# KillSwitch.net
KiCad netlist of a schematic drawn in Altium Designer
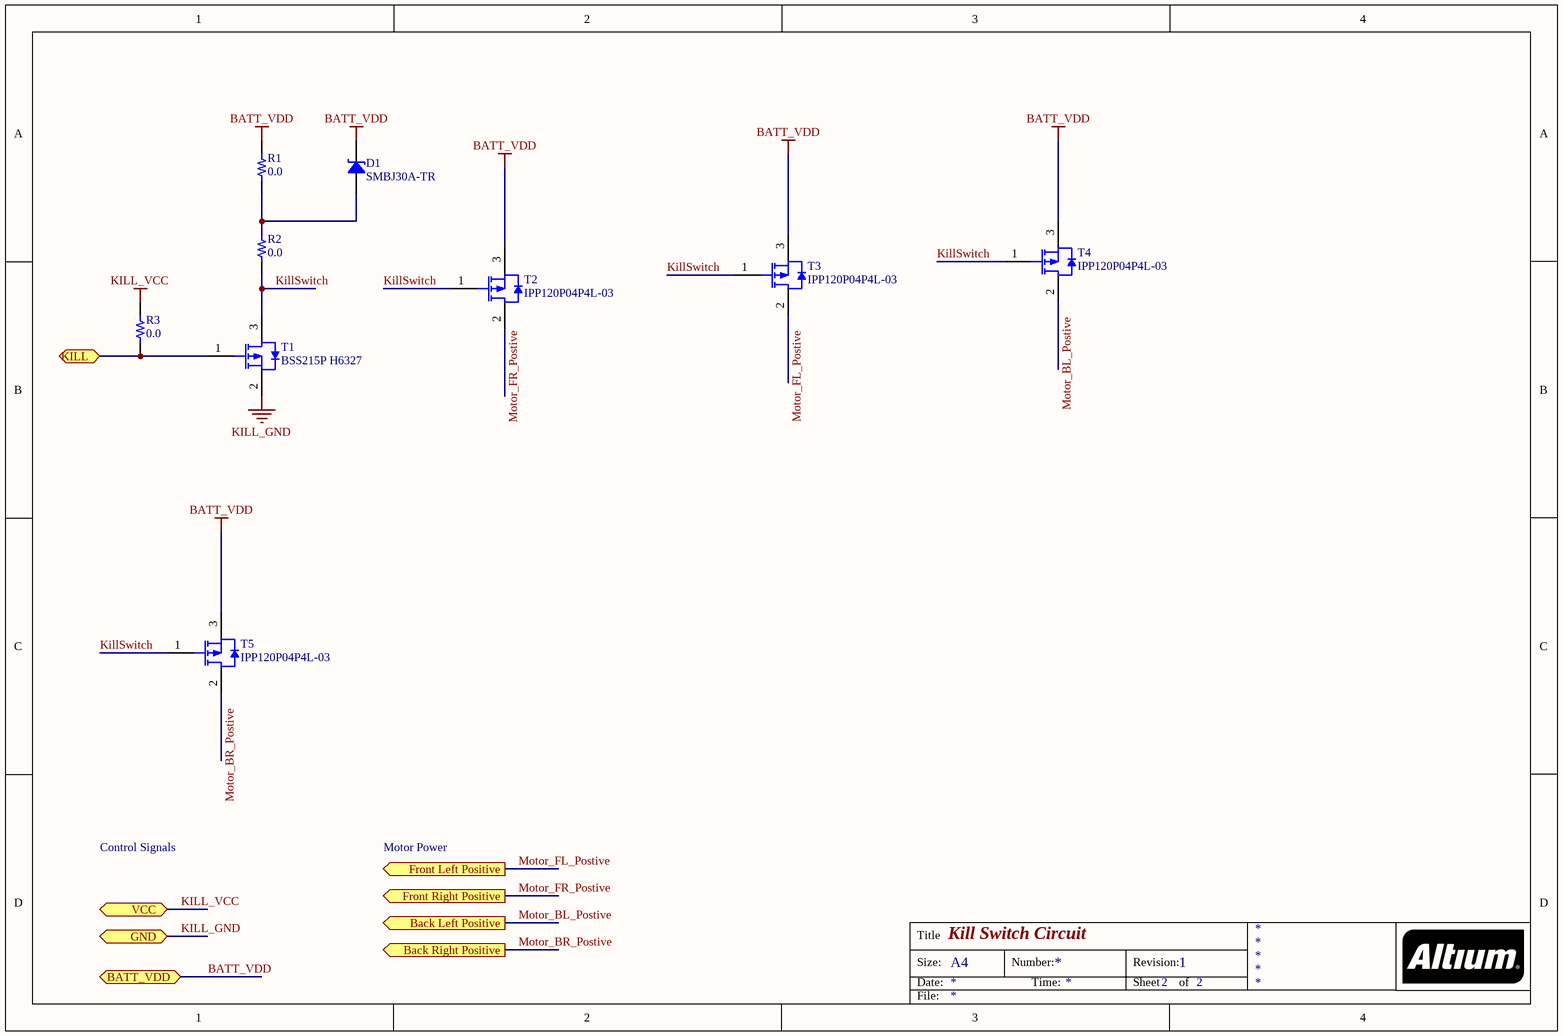
[diagram p0: KillSwitch.SchDoc]

(export (version "E")
  (design (tool "Eeschema 10.0.6"))
  (components
    (comp (ref "D1")
      (value "SMBJ30A-TR")
      (footprint "ST DO214AA SMB")
      (description "TVS DIODE 30VWM 64.3VC SMB")
      (fields (field (name "MANUFACTURER") "STMicroelectronics"))
      (libsource (lib "Celestial Library Database") (part "Diode Zener"))
    )
    (comp (ref "R1")
      (value "0.0")
      (footprint "RES 0603/1608")
      (description "RES SMD 0.0 OHM JUMPER 1/2W 0603")
      (fields (field (name "PART NUMBER") "5110") (field (name "MANUFACTURER") "Keystone Electronics"))
      (libsource (lib "Celestial Library Database") (part "Resistor"))
    )
    (comp (ref "R2")
      (value "0.0")
      (footprint "RES 0603/1608")
      (description "RES SMD 0.0 OHM JUMPER 1/2W 0603")
      (fields (field (name "PART NUMBER") "5110") (field (name "MANUFACTURER") "Keystone Electronics"))
      (libsource (lib "Celestial Library Database") (part "Resistor"))
    )
    (comp (ref "R3")
      (value "0.0")
      (footprint "RES 0603/1608")
      (description "RES SMD 0.0 OHM JUMPER 1/2W 0603")
      (fields (field (name "PART NUMBER") "5110") (field (name "MANUFACTURER") "Keystone Electronics"))
      (libsource (lib "Celestial Library Database") (part "Resistor"))
    )
    (comp (ref "T1")
      (value "BSS215P H6327")
      (footprint "INF-PG-SOT23_N")
      (fields (field (name "MANUFACTURER") "Infineon"))
      (libsource (lib "Infineon_Power_MOSFET") (part "BSS215P H6327"))
    )
    (comp (ref "T2")
      (value "IPP120P04P4L-03")
      (footprint "INF-PG-TO220-3-1")
      (description "OptiMOS-P2 Power-Transistor, -40 V VDS, -120 A ID, PG-TO220-3-1, Tube, Green")
      (fields (field (name "MANUFACTURER") "Infineon"))
      (libsource (lib "Infineon_Power_MOSFET") (part "IPP120P04P4L-03"))
    )
    (comp (ref "T3")
      (value "IPP120P04P4L-03")
      (footprint "INF-PG-TO220-3-1")
      (description "OptiMOS-P2 Power-Transistor, -40 V VDS, -120 A ID, PG-TO220-3-1, Tube, Green")
      (fields (field (name "MANUFACTURER") "Infineon"))
      (libsource (lib "Infineon_Power_MOSFET") (part "IPP120P04P4L-03"))
    )
    (comp (ref "T4")
      (value "IPP120P04P4L-03")
      (footprint "INF-PG-TO220-3-1")
      (description "OptiMOS-P2 Power-Transistor, -40 V VDS, -120 A ID, PG-TO220-3-1, Tube, Green")
      (fields (field (name "MANUFACTURER") "Infineon"))
      (libsource (lib "Infineon_Power_MOSFET") (part "IPP120P04P4L-03"))
    )
    (comp (ref "T5")
      (value "IPP120P04P4L-03")
      (footprint "INF-PG-TO220-3-1")
      (description "OptiMOS-P2 Power-Transistor, -40 V VDS, -120 A ID, PG-TO220-3-1, Tube, Green")
      (fields (field (name "MANUFACTURER") "Infineon"))
      (libsource (lib "Infineon_Power_MOSFET") (part "IPP120P04P4L-03"))
    )
  )
  (nets
    (net (code "1") (name "/KILL") (class "Default")
      (node (ref "R3") (pin "1") (pinfunction "1_1") (pintype "passive"))
      (node (ref "T1") (pin "1") (pinfunction "GATE_1") (pintype "passive"))
    )
    (net (code "2") (name "/KillSwitch") (class "Default")
      (node (ref "R2") (pin "1") (pinfunction "1_1") (pintype "passive"))
      (node (ref "T1") (pin "3") (pinfunction "DRAIN_3") (pintype "passive"))
      (node (ref "T2") (pin "1") (pinfunction "GATE_1") (pintype "passive"))
      (node (ref "T3") (pin "1") (pinfunction "GATE_1") (pintype "passive"))
      (node (ref "T4") (pin "1") (pinfunction "GATE_1") (pintype "passive"))
      (node (ref "T5") (pin "1") (pinfunction "GATE_1") (pintype "passive"))
    )
    (net (code "3") (name "/Motor_BL_Postive") (class "Default")
      (node (ref "T4") (pin "2") (pinfunction "DRAIN_2") (pintype "passive"))
    )
    (net (code "4") (name "/Motor_BR_Postive") (class "Default")
      (node (ref "T5") (pin "2") (pinfunction "DRAIN_2") (pintype "passive"))
    )
    (net (code "5") (name "/Motor_FL_Postive") (class "Default")
      (node (ref "T3") (pin "2") (pinfunction "DRAIN_2") (pintype "passive"))
    )
    (net (code "6") (name "/Motor_FR_Postive") (class "Default")
      (node (ref "T2") (pin "2") (pinfunction "DRAIN_2") (pintype "passive"))
    )
    (net (code "7") (name "BATT_VDD") (class "Default")
      (node (ref "D1") (pin "2") (pinfunction "2_2") (pintype "passive"))
      (node (ref "R1") (pin "2") (pinfunction "2_2") (pintype "passive"))
      (node (ref "T2") (pin "3") (pinfunction "SOURCE_3") (pintype "passive"))
      (node (ref "T3") (pin "3") (pinfunction "SOURCE_3") (pintype "passive"))
      (node (ref "T4") (pin "3") (pinfunction "SOURCE_3") (pintype "passive"))
      (node (ref "T5") (pin "3") (pinfunction "SOURCE_3") (pintype "passive"))
    )
    (net (code "8") (name "KILL_GND") (class "Default")
      (node (ref "T1") (pin "2") (pinfunction "SOURCE_2") (pintype "passive"))
    )
    (net (code "9") (name "KILL_VCC") (class "Default")
      (node (ref "R3") (pin "2") (pinfunction "2_2") (pintype "passive"))
    )
    (net (code "10") (name "Net-(D1-Pad1)") (class "Default")
      (node (ref "D1") (pin "1") (pinfunction "1_1") (pintype "passive"))
      (node (ref "R1") (pin "1") (pinfunction "1_1") (pintype "passive"))
      (node (ref "R2") (pin "2") (pinfunction "2_2") (pintype "passive"))
    )
  )
)
